# dsky_md_2_2v.net
KiCad netlist of a schematic drawn in EAGLE
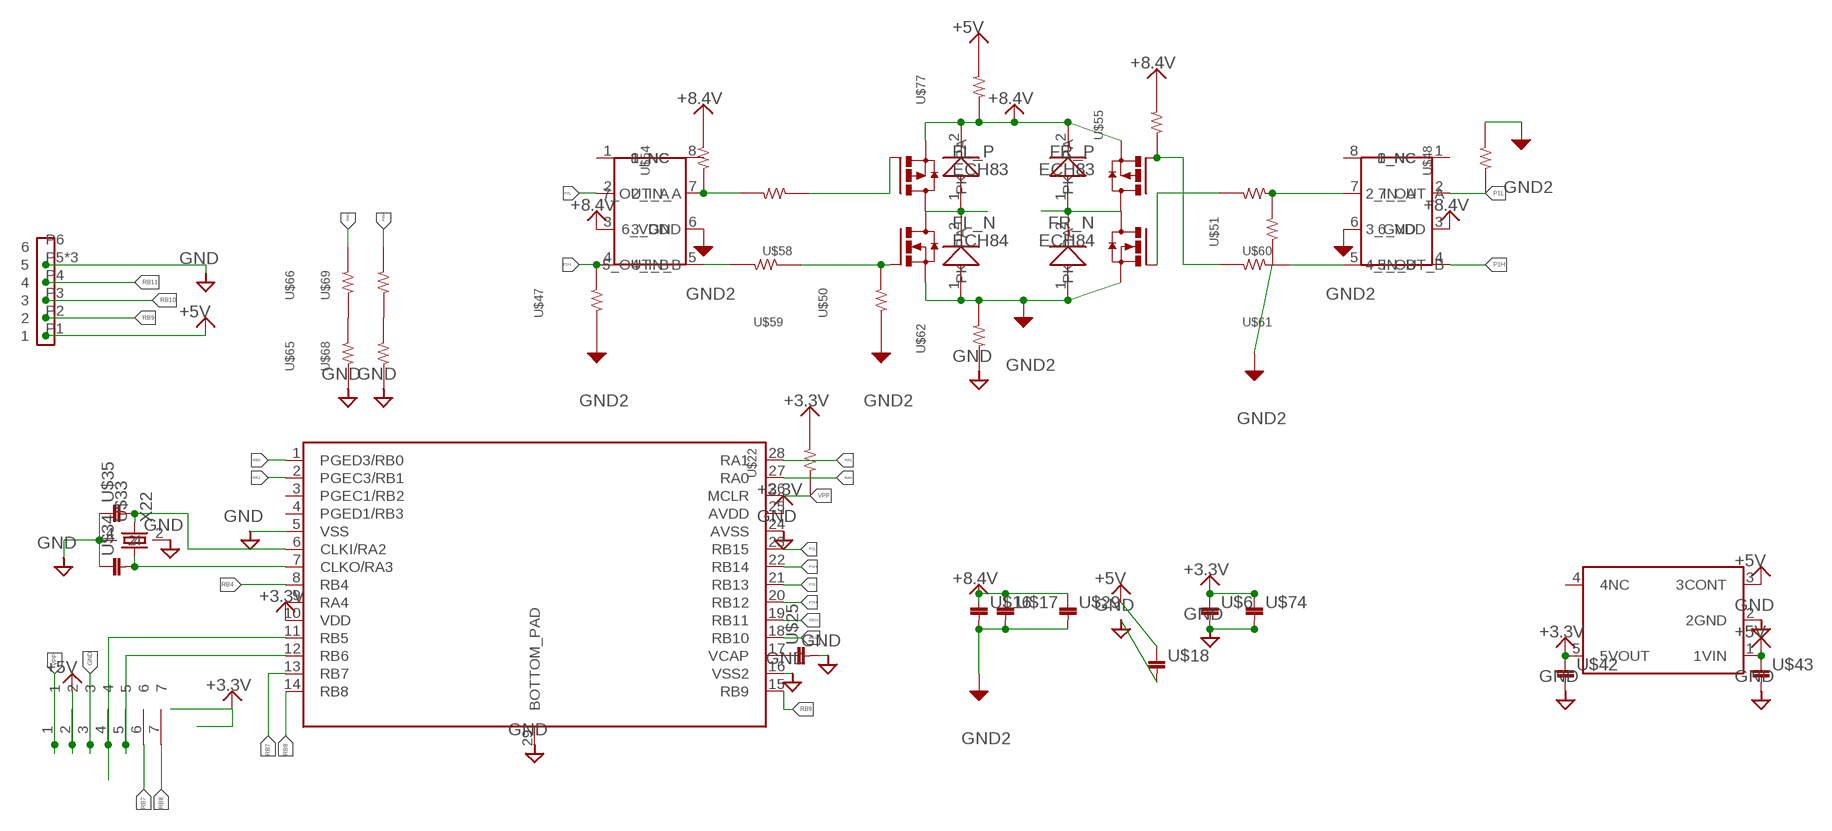
[diagram p0: schematic, sheet 1]

(export (version "E")
  (design (tool "Eeschema 10.0.6"))
  (components
    (comp (ref "FL_N")
      (value "ECH84")
      (footprint "eagle-import:ECH8")
      (libsource (lib "eagle-import") (part "ECH84"))
    )
    (comp (ref "FL_P")
      (value "ECH83")
      (footprint "eagle-import:ECH8")
      (libsource (lib "eagle-import") (part "ECH83"))
    )
    (comp (ref "FR_N")
      (value "ECH84")
      (footprint "eagle-import:ECH8")
      (libsource (lib "eagle-import") (part "ECH84"))
    )
    (comp (ref "FR_P")
      (value "ECH83")
      (footprint "eagle-import:ECH8")
      (libsource (lib "eagle-import") (part "ECH83"))
    )
    (comp (ref "IC_L")
      (value "TC1427COA")
      (footprint "eagle-import:SOIC8")
      (libsource (lib "eagle-import") (part "TC1427COA"))
    )
    (comp (ref "IC_R")
      (value "TC1427COA")
      (footprint "eagle-import:SOIC8")
      (libsource (lib "eagle-import") (part "TC1427COA"))
    )
    (comp (ref "U$3")
      (value "PIN_HEADER_7")
      (footprint "eagle-import:PIN_HEADER_7")
      (libsource (lib "eagle-import") (part "PIN_HEADER_7"))
    )
    (comp (ref "U$5")
      (value "DSPIC33EP32MC202")
      (footprint "eagle-import:QFN-S28_6X6MC")
      (libsource (lib "eagle-import") (part "DSPIC33EP32MC202"))
    )
    (comp (ref "U$6")
      (value "1608")
      (footprint "eagle-import:1608")
      (libsource (lib "eagle-import") (part "1608"))
    )
    (comp (ref "U$16")
      (value "1608")
      (footprint "eagle-import:1608")
      (libsource (lib "eagle-import") (part "1608"))
    )
    (comp (ref "U$17")
      (value "1608")
      (footprint "eagle-import:1608")
      (libsource (lib "eagle-import") (part "1608"))
    )
    (comp (ref "U$18")
      (value "1608")
      (footprint "eagle-import:1608")
      (libsource (lib "eagle-import") (part "1608"))
    )
    (comp (ref "U$22")
      (value "RESISTOR__SMD")
      (footprint "eagle-import:1608")
      (libsource (lib "eagle-import") (part "RESISTOR__SMD"))
    )
    (comp (ref "U$25")
      (value "1608")
      (footprint "eagle-import:1608")
      (libsource (lib "eagle-import") (part "1608"))
    )
    (comp (ref "U$29")
      (value "2012")
      (footprint "eagle-import:2012")
      (libsource (lib "eagle-import") (part "2012"))
    )
    (comp (ref "U$30")
      (value "TAR5SB")
      (footprint "eagle-import:SSOP5-P-0.95")
      (libsource (lib "eagle-import") (part "TAR5SB"))
    )
    (comp (ref "U$33")
      (value "X22")
      (footprint "eagle-import:SMD_X22")
      (libsource (lib "eagle-import") (part "X22"))
    )
    (comp (ref "U$34")
      (value "1608")
      (footprint "eagle-import:1608")
      (libsource (lib "eagle-import") (part "1608"))
    )
    (comp (ref "U$35")
      (value "1608")
      (footprint "eagle-import:1608")
      (libsource (lib "eagle-import") (part "1608"))
    )
    (comp (ref "U$42")
      (value "1608")
      (footprint "eagle-import:1608")
      (libsource (lib "eagle-import") (part "1608"))
    )
    (comp (ref "U$43")
      (value "1608")
      (footprint "eagle-import:1608")
      (libsource (lib "eagle-import") (part "1608"))
    )
    (comp (ref "U$44")
      (value "FH12-6S-0.5")
      (footprint "eagle-import:FPC6")
      (libsource (lib "eagle-import") (part "FH12-6S-0.5"))
    )
    (comp (ref "U$47")
      (value "RESISTOR__SMD")
      (footprint "eagle-import:1608")
      (libsource (lib "eagle-import") (part "RESISTOR__SMD"))
    )
    (comp (ref "U$48")
      (value "RESISTOR__SMD")
      (footprint "eagle-import:1608")
      (libsource (lib "eagle-import") (part "RESISTOR__SMD"))
    )
    (comp (ref "U$50")
      (value "RESISTOR__SMD")
      (footprint "eagle-import:1608")
      (libsource (lib "eagle-import") (part "RESISTOR__SMD"))
    )
    (comp (ref "U$51")
      (value "RESISTOR__SMD")
      (footprint "eagle-import:1608")
      (libsource (lib "eagle-import") (part "RESISTOR__SMD"))
    )
    (comp (ref "U$54")
      (value "RESISTOR__SMD")
      (footprint "eagle-import:1608")
      (libsource (lib "eagle-import") (part "RESISTOR__SMD"))
    )
    (comp (ref "U$55")
      (value "RESISTOR__SMD")
      (footprint "eagle-import:1608")
      (libsource (lib "eagle-import") (part "RESISTOR__SMD"))
    )
    (comp (ref "U$58")
      (value "RESISTOR__SMD")
      (footprint "eagle-import:1608")
      (libsource (lib "eagle-import") (part "RESISTOR__SMD"))
    )
    (comp (ref "U$59")
      (value "RESISTOR__SMD")
      (footprint "eagle-import:1608")
      (libsource (lib "eagle-import") (part "RESISTOR__SMD"))
    )
    (comp (ref "U$60")
      (value "RESISTOR__SMD")
      (footprint "eagle-import:1608")
      (libsource (lib "eagle-import") (part "RESISTOR__SMD"))
    )
    (comp (ref "U$61")
      (value "RESISTOR__SMD")
      (footprint "eagle-import:1608")
      (libsource (lib "eagle-import") (part "RESISTOR__SMD"))
    )
    (comp (ref "U$62")
      (value "RESISTOR__SMD")
      (footprint "eagle-import:1608")
      (libsource (lib "eagle-import") (part "RESISTOR__SMD"))
    )
    (comp (ref "U$65")
      (value "RESISTOR__SMD")
      (footprint "eagle-import:1608")
      (libsource (lib "eagle-import") (part "RESISTOR__SMD"))
    )
    (comp (ref "U$66")
      (value "RESISTOR__SMD")
      (footprint "eagle-import:1608")
      (libsource (lib "eagle-import") (part "RESISTOR__SMD"))
    )
    (comp (ref "U$68")
      (value "RESISTOR__SMD")
      (footprint "eagle-import:1608")
      (libsource (lib "eagle-import") (part "RESISTOR__SMD"))
    )
    (comp (ref "U$69")
      (value "RESISTOR__SMD")
      (footprint "eagle-import:1608")
      (libsource (lib "eagle-import") (part "RESISTOR__SMD"))
    )
    (comp (ref "U$70")
      (value "SS2040")
      (footprint "eagle-import:SOD-123FL")
      (libsource (lib "eagle-import") (part "SS2040"))
    )
    (comp (ref "U$71")
      (value "SS2040")
      (footprint "eagle-import:SOD-123FL")
      (libsource (lib "eagle-import") (part "SS2040"))
    )
    (comp (ref "U$72")
      (value "SS2040")
      (footprint "eagle-import:SOD-123FL")
      (libsource (lib "eagle-import") (part "SS2040"))
    )
    (comp (ref "U$73")
      (value "SS2040")
      (footprint "eagle-import:SOD-123FL")
      (libsource (lib "eagle-import") (part "SS2040"))
    )
    (comp (ref "U$74")
      (value "1608")
      (footprint "eagle-import:1608")
      (libsource (lib "eagle-import") (part "1608"))
    )
    (comp (ref "U$77")
      (value "RESISTOR__SMD")
      (footprint "eagle-import:1608")
      (libsource (lib "eagle-import") (part "RESISTOR__SMD"))
    )
  )
  (nets
    (net (code "1") (name "+3.3V") (class "Default")
      (node (ref "U$22") (pin "2") (pinfunction "P$2_2") (pintype "passive"))
      (node (ref "U$30") (pin "5") (pinfunction "5VOUT_5") (pintype "bidirectional"))
      (node (ref "U$42") (pin "P$1") (pinfunction "1_P$1") (pintype "passive"))
      (node (ref "U$5") (pin "10") (pinfunction "VDD_10") (pintype "bidirectional"))
      (node (ref "U$5") (pin "25") (pinfunction "AVDD_25") (pintype "bidirectional"))
      (node (ref "U$6") (pin "P$1") (pinfunction "1_P$1") (pintype "passive"))
      (node (ref "U$74") (pin "P$1") (pinfunction "1_P$1") (pintype "passive"))
    )
    (net (code "2") (name "+5V") (class "Default")
      (node (ref "U$18") (pin "P$1") (pinfunction "1_P$1") (pintype "passive"))
      (node (ref "U$3") (pin "2") (pinfunction "2_2") (pintype "bidirectional"))
      (node (ref "U$30") (pin "1") (pinfunction "1VIN_1") (pintype "bidirectional"))
      (node (ref "U$30") (pin "3") (pinfunction "3CONT_3") (pintype "bidirectional"))
      (node (ref "U$43") (pin "P$1") (pinfunction "1_P$1") (pintype "passive"))
      (node (ref "U$44") (pin "P1") (pinfunction "1_P1") (pintype "bidirectional"))
      (node (ref "U$77") (pin "2") (pinfunction "P$2_2") (pintype "passive"))
    )
    (net (code "3") (name "+8.4V") (class "Default")
      (node (ref "FL_P") (pin "1") (pinfunction "S_1") (pintype "passive"))
      (node (ref "FL_P") (pin "2") (pinfunction "S_2") (pintype "passive"))
      (node (ref "FL_P") (pin "3") (pinfunction "S_3") (pintype "passive"))
      (node (ref "FR_P") (pin "1") (pinfunction "S_1") (pintype "passive"))
      (node (ref "FR_P") (pin "2") (pinfunction "S_2") (pintype "passive"))
      (node (ref "FR_P") (pin "3") (pinfunction "S_3") (pintype "passive"))
      (node (ref "IC_L") (pin "3") (pinfunction "3_GND_3") (pintype "bidirectional"))
      (node (ref "IC_R") (pin "3") (pinfunction "3_GND_3") (pintype "bidirectional"))
      (node (ref "U$16") (pin "P$1") (pinfunction "1_P$1") (pintype "passive"))
      (node (ref "U$17") (pin "P$1") (pinfunction "1_P$1") (pintype "passive"))
      (node (ref "U$29") (pin "1") (pinfunction "1_1") (pintype "passive"))
      (node (ref "U$54") (pin "2") (pinfunction "P$2_2") (pintype "passive"))
      (node (ref "U$55") (pin "2") (pinfunction "P$2_2") (pintype "passive"))
      (node (ref "U$70") (pin "2") (pinfunction "PK_2") (pintype "bidirectional"))
      (node (ref "U$73") (pin "2") (pinfunction "PK_2") (pintype "bidirectional"))
      (node (ref "U$77") (pin "1") (pinfunction "P$1_1") (pintype "passive"))
    )
    (net (code "4") (name "GND") (class "Default")
      (node (ref "U$18") (pin "P$2") (pinfunction "2_P$2") (pintype "passive"))
      (node (ref "U$25") (pin "P$2") (pinfunction "2_P$2") (pintype "passive"))
      (node (ref "U$3") (pin "3") (pinfunction "3_3") (pintype "bidirectional"))
      (node (ref "U$30") (pin "2") (pinfunction "2GND_2") (pintype "bidirectional"))
      (node (ref "U$33") (pin "2") (pinfunction "2_2") (pintype "bidirectional"))
      (node (ref "U$33") (pin "4") (pinfunction "4_4") (pintype "bidirectional"))
      (node (ref "U$34") (pin "P$1") (pinfunction "1_P$1") (pintype "passive"))
      (node (ref "U$35") (pin "P$1") (pinfunction "1_P$1") (pintype "passive"))
      (node (ref "U$42") (pin "P$2") (pinfunction "2_P$2") (pintype "passive"))
      (node (ref "U$43") (pin "P$2") (pinfunction "2_P$2") (pintype "passive"))
      (node (ref "U$44") (pin "P5") (pinfunction "5_P5") (pintype "bidirectional"))
      (node (ref "U$44") (pin "P_NC1") (pinfunction "5_P_NC1") (pintype "bidirectional"))
      (node (ref "U$44") (pin "P_NC2") (pinfunction "5_P_NC2") (pintype "bidirectional"))
      (node (ref "U$5") (pin "16") (pinfunction "VSS2_16") (pintype "power_in"))
      (node (ref "U$5") (pin "24") (pinfunction "AVSS_24") (pintype "bidirectional"))
      (node (ref "U$5") (pin "29") (pinfunction "BOTTOM_PAD_29") (pintype "bidirectional"))
      (node (ref "U$5") (pin "5") (pinfunction "VSS_5") (pintype "power_in"))
      (node (ref "U$6") (pin "P$2") (pinfunction "2_P$2") (pintype "passive"))
      (node (ref "U$62") (pin "1") (pinfunction "P$1_1") (pintype "passive"))
      (node (ref "U$65") (pin "1") (pinfunction "P$1_1") (pintype "passive"))
      (node (ref "U$68") (pin "1") (pinfunction "P$1_1") (pintype "passive"))
      (node (ref "U$74") (pin "P$2") (pinfunction "2_P$2") (pintype "passive"))
    )
    (net (code "5") (name "GND2") (class "Default")
      (node (ref "FL_N") (pin "1") (pinfunction "S_1") (pintype "passive"))
      (node (ref "FL_N") (pin "2") (pinfunction "S_2") (pintype "passive"))
      (node (ref "FL_N") (pin "3") (pinfunction "S_3") (pintype "passive"))
      (node (ref "FR_N") (pin "1") (pinfunction "S_1") (pintype "passive"))
      (node (ref "FR_N") (pin "2") (pinfunction "S_2") (pintype "passive"))
      (node (ref "FR_N") (pin "3") (pinfunction "S_3") (pintype "passive"))
      (node (ref "IC_L") (pin "6") (pinfunction "6_VDD_6") (pintype "bidirectional"))
      (node (ref "IC_R") (pin "6") (pinfunction "6_VDD_6") (pintype "bidirectional"))
      (node (ref "U$16") (pin "P$2") (pinfunction "2_P$2") (pintype "passive"))
      (node (ref "U$17") (pin "P$2") (pinfunction "2_P$2") (pintype "passive"))
      (node (ref "U$29") (pin "2") (pinfunction "2_2") (pintype "passive"))
      (node (ref "U$47") (pin "1") (pinfunction "P$1_1") (pintype "passive"))
      (node (ref "U$48") (pin "2") (pinfunction "P$2_2") (pintype "passive"))
      (node (ref "U$50") (pin "1") (pinfunction "P$1_1") (pintype "passive"))
      (node (ref "U$51") (pin "1") (pinfunction "P$1_1") (pintype "passive"))
      (node (ref "U$62") (pin "2") (pinfunction "P$2_2") (pintype "passive"))
      (node (ref "U$71") (pin "1") (pinfunction "PA_1") (pintype "bidirectional"))
      (node (ref "U$72") (pin "1") (pinfunction "PA_1") (pintype "bidirectional"))
    )
    (net (code "6") (name "Net-(FL_N-G)") (class "Default")
      (node (ref "FL_N") (pin "4") (pinfunction "G_4") (pintype "passive"))
      (node (ref "U$50") (pin "2") (pinfunction "P$2_2") (pintype "passive"))
      (node (ref "U$59") (pin "1") (pinfunction "P$1_1") (pintype "passive"))
    )
    (net (code "7") (name "Net-(FL_P-G)") (class "Default")
      (node (ref "FL_P") (pin "4") (pinfunction "G_4") (pintype "passive"))
      (node (ref "U$58") (pin "1") (pinfunction "P$1_1") (pintype "passive"))
    )
    (net (code "8") (name "Net-(FR_N-G)") (class "Default")
      (node (ref "FR_N") (pin "4") (pinfunction "G_4") (pintype "passive"))
      (node (ref "U$60") (pin "2") (pinfunction "P$2_2") (pintype "passive"))
    )
    (net (code "9") (name "Net-(FR_P-G)") (class "Default")
      (node (ref "FR_P") (pin "4") (pinfunction "G_4") (pintype "passive"))
      (node (ref "U$55") (pin "1") (pinfunction "P$1_1") (pintype "passive"))
      (node (ref "U$61") (pin "2") (pinfunction "P$2_2") (pintype "passive"))
    )
    (net (code "10") (name "Net-(IC_L-5_OUT_B)") (class "Default")
      (node (ref "IC_L") (pin "5") (pinfunction "5_OUT_B_5") (pintype "bidirectional"))
      (node (ref "U$59") (pin "2") (pinfunction "P$2_2") (pintype "passive"))
    )
    (net (code "11") (name "Net-(IC_L-7_OUT_A)") (class "Default")
      (node (ref "IC_L") (pin "7") (pinfunction "7_OUT_A_7") (pintype "bidirectional"))
      (node (ref "U$54") (pin "1") (pinfunction "P$1_1") (pintype "passive"))
      (node (ref "U$58") (pin "2") (pinfunction "P$2_2") (pintype "passive"))
    )
    (net (code "12") (name "Net-(IC_R-5_OUT_B)") (class "Default")
      (node (ref "IC_R") (pin "5") (pinfunction "5_OUT_B_5") (pintype "bidirectional"))
      (node (ref "U$61") (pin "1") (pinfunction "P$1_1") (pintype "passive"))
    )
    (net (code "13") (name "Net-(IC_R-7_OUT_A)") (class "Default")
      (node (ref "IC_R") (pin "7") (pinfunction "7_OUT_A_7") (pintype "bidirectional"))
      (node (ref "U$51") (pin "2") (pinfunction "P$2_2") (pintype "passive"))
      (node (ref "U$60") (pin "1") (pinfunction "P$1_1") (pintype "passive"))
    )
    (net (code "14") (name "Net-(U$5-RB5)") (class "Default")
      (node (ref "U$3") (pin "4") (pinfunction "4_4") (pintype "bidirectional"))
      (node (ref "U$5") (pin "11") (pinfunction "RB5_11") (pintype "bidirectional"))
    )
    (net (code "15") (name "Net-(U$5-RB6)") (class "Default")
      (node (ref "U$3") (pin "5") (pinfunction "5_5") (pintype "bidirectional"))
      (node (ref "U$5") (pin "12") (pinfunction "RB6_12") (pintype "bidirectional"))
    )
    (net (code "16") (name "Net-(U$25-1)") (class "Default")
      (node (ref "U$25") (pin "P$1") (pinfunction "1_P$1") (pintype "passive"))
      (node (ref "U$5") (pin "17") (pinfunction "VCAP_17") (pintype "bidirectional"))
    )
    (net (code "17") (name "Net-(U$34-2)") (class "Default")
      (node (ref "U$33") (pin "1") (pinfunction "1_1") (pintype "passive"))
      (node (ref "U$34") (pin "P$2") (pinfunction "2_P$2") (pintype "passive"))
      (node (ref "U$5") (pin "7") (pinfunction "CLKO/RA3_7") (pintype "bidirectional"))
    )
    (net (code "18") (name "Net-(U$35-2)") (class "Default")
      (node (ref "U$33") (pin "3") (pinfunction "3_3") (pintype "passive"))
      (node (ref "U$35") (pin "P$2") (pinfunction "2_P$2") (pintype "passive"))
      (node (ref "U$5") (pin "6") (pinfunction "CLKI/RA2_6") (pintype "bidirectional"))
    )
    (net (code "19") (name "Net-(U$65-P$2)") (class "Default")
      (node (ref "U$65") (pin "2") (pinfunction "P$2_2") (pintype "passive"))
      (node (ref "U$66") (pin "1") (pinfunction "P$1_1") (pintype "passive"))
    )
    (net (code "20") (name "Net-(U$68-P$2)") (class "Default")
      (node (ref "U$68") (pin "2") (pinfunction "P$2_2") (pintype "passive"))
      (node (ref "U$69") (pin "1") (pinfunction "P$1_1") (pintype "passive"))
    )
    (net (code "21") (name "Net-(U$70-PA)") (class "Default")
      (node (ref "FL_N") (pin "5") (pinfunction "D_5") (pintype "passive"))
      (node (ref "FL_N") (pin "6") (pinfunction "D_6") (pintype "passive"))
      (node (ref "FL_N") (pin "7") (pinfunction "D_7") (pintype "passive"))
      (node (ref "FL_N") (pin "8") (pinfunction "D_8") (pintype "passive"))
      (node (ref "FL_P") (pin "5") (pinfunction "D_5") (pintype "passive"))
      (node (ref "FL_P") (pin "6") (pinfunction "D_6") (pintype "passive"))
      (node (ref "FL_P") (pin "7") (pinfunction "D_7") (pintype "passive"))
      (node (ref "FL_P") (pin "8") (pinfunction "D_8") (pintype "passive"))
      (node (ref "U$70") (pin "1") (pinfunction "PA_1") (pintype "bidirectional"))
      (node (ref "U$71") (pin "2") (pinfunction "PK_2") (pintype "bidirectional"))
    )
    (net (code "22") (name "Net-(U$72-PK)") (class "Default")
      (node (ref "FR_N") (pin "5") (pinfunction "D_5") (pintype "passive"))
      (node (ref "FR_N") (pin "6") (pinfunction "D_6") (pintype "passive"))
      (node (ref "FR_N") (pin "7") (pinfunction "D_7") (pintype "passive"))
      (node (ref "FR_N") (pin "8") (pinfunction "D_8") (pintype "passive"))
      (node (ref "FR_P") (pin "5") (pinfunction "D_5") (pintype "passive"))
      (node (ref "FR_P") (pin "6") (pinfunction "D_6") (pintype "passive"))
      (node (ref "FR_P") (pin "7") (pinfunction "D_7") (pintype "passive"))
      (node (ref "FR_P") (pin "8") (pinfunction "D_8") (pintype "passive"))
      (node (ref "U$72") (pin "2") (pinfunction "PK_2") (pintype "bidirectional"))
      (node (ref "U$73") (pin "1") (pinfunction "PA_1") (pintype "bidirectional"))
    )
    (net (code "23") (name "P1H") (class "Default")
      (node (ref "IC_R") (pin "4") (pinfunction "4_IN_B_4") (pintype "bidirectional"))
      (node (ref "U$5") (pin "22") (pinfunction "RB14_22") (pintype "bidirectional"))
    )
    (net (code "24") (name "P1L") (class "Default")
      (node (ref "IC_R") (pin "2") (pinfunction "2_IN_A_2") (pintype "bidirectional"))
      (node (ref "U$48") (pin "1") (pinfunction "P$1_1") (pintype "passive"))
      (node (ref "U$5") (pin "23") (pinfunction "RB15_23") (pintype "bidirectional"))
    )
    (net (code "25") (name "P2H") (class "Default")
      (node (ref "IC_L") (pin "4") (pinfunction "4_IN_B_4") (pintype "bidirectional"))
      (node (ref "U$47") (pin "2") (pinfunction "P$2_2") (pintype "passive"))
      (node (ref "U$5") (pin "20") (pinfunction "RB12_20") (pintype "bidirectional"))
    )
    (net (code "26") (name "P2L") (class "Default")
      (node (ref "IC_L") (pin "2") (pinfunction "2_IN_A_2") (pintype "bidirectional"))
      (node (ref "U$5") (pin "21") (pinfunction "RB13_21") (pintype "bidirectional"))
    )
    (net (code "27") (name "RA0") (class "Default")
      (node (ref "U$5") (pin "27") (pinfunction "RA0_27") (pintype "bidirectional"))
      (node (ref "U$66") (pin "2") (pinfunction "P$2_2") (pintype "passive"))
    )
    (net (code "28") (name "RA1") (class "Default")
      (node (ref "U$5") (pin "28") (pinfunction "RA1_28") (pintype "bidirectional"))
    )
    (net (code "29") (name "RB0") (class "Default")
      (node (ref "U$5") (pin "1") (pinfunction "PGED3/RB0_1") (pintype "bidirectional"))
      (node (ref "U$69") (pin "2") (pinfunction "P$2_2") (pintype "passive"))
    )
    (net (code "30") (name "RB1") (class "Default")
      (node (ref "U$5") (pin "2") (pinfunction "PGEC3/RB1_2") (pintype "bidirectional"))
    )
    (net (code "31") (name "RB4") (class "Default")
      (node (ref "U$5") (pin "8") (pinfunction "RB4_8") (pintype "bidirectional"))
    )
    (net (code "32") (name "RB7") (class "Default")
      (node (ref "U$3") (pin "6") (pinfunction "6_6") (pintype "bidirectional"))
      (node (ref "U$5") (pin "13") (pinfunction "RB7_13") (pintype "bidirectional"))
    )
    (net (code "33") (name "RB8") (class "Default")
      (node (ref "U$3") (pin "7") (pinfunction "7_7") (pintype "bidirectional"))
      (node (ref "U$5") (pin "14") (pinfunction "RB8_14") (pintype "bidirectional"))
    )
    (net (code "34") (name "RB9") (class "Default")
      (node (ref "U$44") (pin "P2") (pinfunction "2_P2") (pintype "bidirectional"))
      (node (ref "U$5") (pin "15") (pinfunction "RB9_15") (pintype "bidirectional"))
    )
    (net (code "35") (name "RB10") (class "Default")
      (node (ref "U$44") (pin "P3") (pinfunction "3_P3") (pintype "bidirectional"))
      (node (ref "U$5") (pin "18") (pinfunction "RB10_18") (pintype "bidirectional"))
    )
    (net (code "36") (name "RB11") (class "Default")
      (node (ref "U$44") (pin "P4") (pinfunction "4_P4") (pintype "bidirectional"))
      (node (ref "U$5") (pin "19") (pinfunction "RB11_19") (pintype "bidirectional"))
    )
    (net (code "37") (name "VPP") (class "Default")
      (node (ref "U$22") (pin "1") (pinfunction "P$1_1") (pintype "passive"))
      (node (ref "U$3") (pin "1") (pinfunction "1_1") (pintype "bidirectional"))
      (node (ref "U$5") (pin "26") (pinfunction "MCLR_26") (pintype "bidirectional"))
    )
    (net (code "38") (name "unconnected-(IC_L-1_NC-Pad1)") (class "Default")
      (node (ref "IC_L") (pin "1") (pinfunction "1_NC_1") (pintype "bidirectional"))
    )
    (net (code "39") (name "unconnected-(IC_L-8_NC-Pad8)") (class "Default")
      (node (ref "IC_L") (pin "8") (pinfunction "8_NC_8") (pintype "bidirectional"))
    )
    (net (code "40") (name "unconnected-(IC_R-1_NC-Pad1)") (class "Default")
      (node (ref "IC_R") (pin "1") (pinfunction "1_NC_1") (pintype "bidirectional"))
    )
    (net (code "41") (name "unconnected-(IC_R-8_NC-Pad8)") (class "Default")
      (node (ref "IC_R") (pin "8") (pinfunction "8_NC_8") (pintype "bidirectional"))
    )
    (net (code "42") (name "unconnected-(U$5-PGEC1{slash}RB2-Pad3)") (class "Default")
      (node (ref "U$5") (pin "3") (pinfunction "PGEC1/RB2_3") (pintype "bidirectional"))
    )
    (net (code "43") (name "unconnected-(U$5-PGED1{slash}RB3-Pad4)") (class "Default")
      (node (ref "U$5") (pin "4") (pinfunction "PGED1/RB3_4") (pintype "bidirectional"))
    )
    (net (code "44") (name "unconnected-(U$5-RA4-Pad9)") (class "Default")
      (node (ref "U$5") (pin "9") (pinfunction "RA4_9") (pintype "bidirectional"))
    )
    (net (code "45") (name "unconnected-(U$30-4NC-Pad4)") (class "Default")
      (node (ref "U$30") (pin "4") (pinfunction "4NC_4") (pintype "bidirectional"))
    )
    (net (code "46") (name "unconnected-(U$44-6-PadP6)") (class "Default")
      (node (ref "U$44") (pin "P6") (pinfunction "6_P6") (pintype "bidirectional"))
    )
  )
)
